# mag_encoder_Rev2.net
KiCad netlist of a schematic drawn in EAGLE
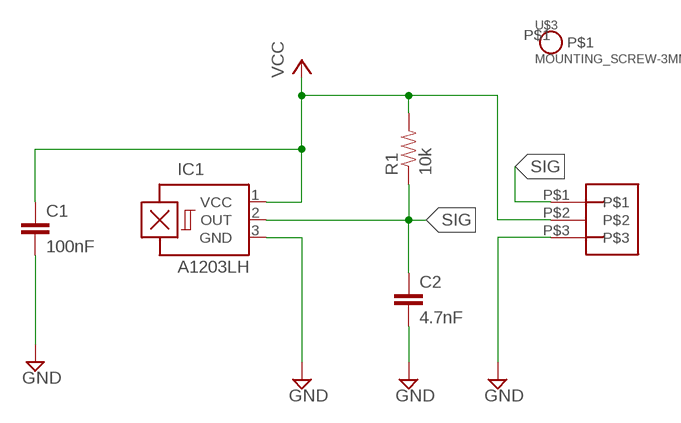
[diagram p0: schematic, sheet 1]

(export (version "E")
  (design (tool "Eeschema 10.0.6"))
  (components
    (comp (ref "C1")
      (value "100nF")
      (footprint "eagle-import:0603-CAP")
      (libsource (lib "eagle-import") (part "CAP0603-CAP"))
    )
    (comp (ref "C2")
      (value "4.7nF")
      (footprint "eagle-import:0603-CAP")
      (libsource (lib "eagle-import") (part "4.7NF-50V-10%(0603)"))
    )
    (comp (ref "IC1")
      (value "A1203LH")
      (footprint "eagle-import:SOT23-W")
      (fields (field (name "MF") "ALLEGRO MICROSYSTEMS, INC.") (field (name "MPN") "A1203LLHLT-T"))
      (libsource (lib "eagle-import") (part "A12?LH03"))
    )
    (comp (ref "R1")
      (value "10k")
      (footprint "eagle-import:0603")
      (libsource (lib "eagle-import") (part "10.5KOHM1/10W1%(0603)"))
    )
    (comp (ref "U$1")
      (value "3_PIN_JST-XH")
      (footprint "eagle-import:3_PIN_JST-XH")
      (libsource (lib "eagle-import") (part "3_PIN_JST-XH"))
    )
    (comp (ref "U$3")
      (value "MOUNTING_SCREW-3MM")
      (footprint "eagle-import:MOUNTING_SCREW-3MM")
      (libsource (lib "eagle-import") (part "MOUNTING_SCREW-3MM"))
    )
  )
  (nets
    (net (code "1") (name "GND") (class "Default")
      (node (ref "C1") (pin "2") (pinfunction "2_2") (pintype "passive"))
      (node (ref "C2") (pin "2") (pinfunction "2_2") (pintype "passive"))
      (node (ref "IC1") (pin "3") (pinfunction "GND_3") (pintype "power_in"))
      (node (ref "U$1") (pin "P$3") (pinfunction "P$3_P$3") (pintype "bidirectional"))
    )
    (net (code "2") (name "SIG") (class "Default")
      (node (ref "C2") (pin "1") (pinfunction "1_1") (pintype "passive"))
      (node (ref "IC1") (pin "2") (pinfunction "OUT_2") (pintype "output"))
      (node (ref "R1") (pin "1") (pinfunction "1_1") (pintype "passive"))
      (node (ref "U$1") (pin "P$1") (pinfunction "P$1_P$1") (pintype "bidirectional"))
    )
    (net (code "3") (name "VCC") (class "Default")
      (node (ref "C1") (pin "1") (pinfunction "1_1") (pintype "passive"))
      (node (ref "IC1") (pin "1") (pinfunction "VCC_1") (pintype "power_in"))
      (node (ref "R1") (pin "2") (pinfunction "2_2") (pintype "passive"))
      (node (ref "U$1") (pin "P$2") (pinfunction "P$2_P$2") (pintype "bidirectional"))
    )
    (net (code "4") (name "unconnected-(U$3-PadP$1)") (class "Default")
      (node (ref "U$3") (pin "P$1") (pinfunction "P$1_P$1") (pintype "bidirectional"))
    )
  )
)
